# MAGI_sSensor.net
KiCad netlist of a schematic drawn in Altium Designer
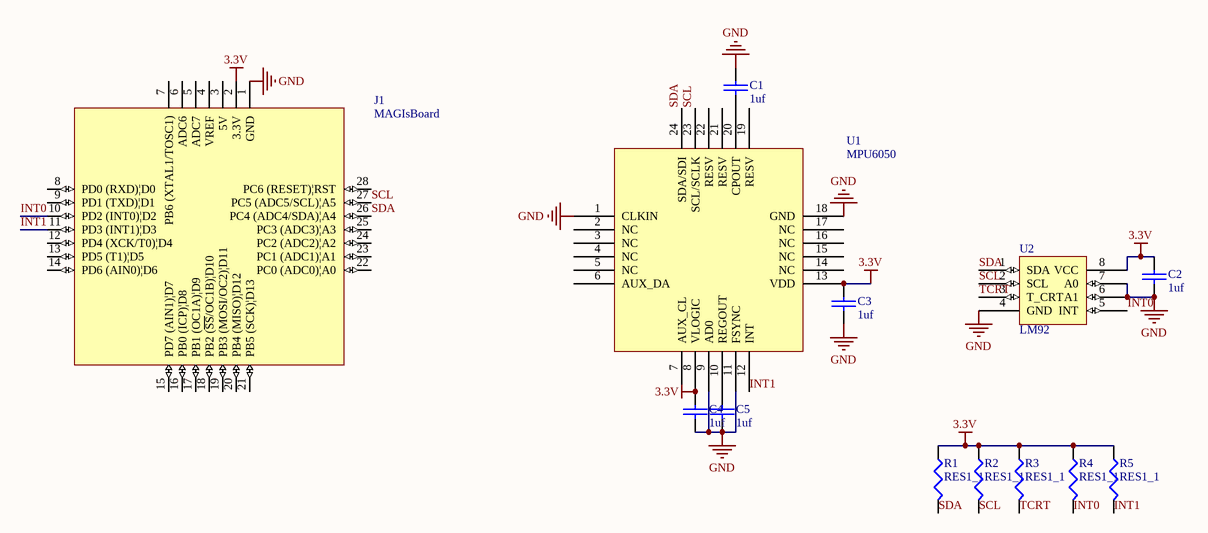
[diagram p0: MAGI'sSensor.SchDoc]

(export (version "E")
  (design (tool "Eeschema 10.0.6"))
  (components
    (comp (ref "C1")
      (value "1uf")
      (footprint "6-0805_N")
      (description "Capacitor")
      (libsource (lib "电容器") (part "CAP_1"))
    )
    (comp (ref "C2")
      (value "1uf")
      (footprint "6-0805_N")
      (description "Capacitor")
      (libsource (lib "电容器") (part "CAP_1"))
    )
    (comp (ref "C3")
      (value "1uf")
      (footprint "6-0805_N")
      (description "Capacitor")
      (libsource (lib "电容器") (part "CAP_1"))
    )
    (comp (ref "C4")
      (value "1uf")
      (footprint "6-0805_N")
      (description "Capacitor")
      (libsource (lib "电容器") (part "CAP_1"))
    )
    (comp (ref "C5")
      (value "1uf")
      (footprint "6-0805_N")
      (description "Capacitor")
      (libsource (lib "电容器") (part "CAP_1"))
    )
    (comp (ref "J1")
      (value "MAGIsBoard")
      (footprint "MAGIsBoard")
      (libsource (lib "MAGIsBoard") (part "MAGIsBoard"))
    )
    (comp (ref "R1") (value "RES1_1") (footprint "6-0805_N") (libsource (lib "电阻器") (part "RES1_1")))
    (comp (ref "R2") (value "RES1_1") (footprint "6-0805_N") (libsource (lib "电阻器") (part "RES1_1")))
    (comp (ref "R3") (value "RES1_1") (footprint "6-0805_N") (libsource (lib "电阻器") (part "RES1_1")))
    (comp (ref "R4") (value "RES1_1") (footprint "6-0805_N") (libsource (lib "电阻器") (part "RES1_1")))
    (comp (ref "R5") (value "RES1_1") (footprint "6-0805_N") (libsource (lib "电阻器") (part "RES1_1")))
    (comp (ref "U1") (value "MPU6050") (footprint "MPU6050") (libsource (lib "Sensor") (part "MPU6050")))
    (comp (ref "U2") (value "LM92") (footprint "8S1_N") (libsource (lib "ATtiny13A") (part "ATtiny13A")))
  )
  (nets
    (net (code "1") (name "/INT0") (class "Default")
      (node (ref "J1") (pin "10") (pinfunction "PD2_(INT0)¦D2_10") (pintype "bidirectional"))
      (node (ref "R4") (pin "2") (pinfunction "2_2") (pintype "passive"))
      (node (ref "U2") (pin "5") (pinfunction "INT_5") (pintype "bidirectional"))
    )
    (net (code "2") (name "/INT1") (class "Default")
      (node (ref "J1") (pin "11") (pinfunction "PD3_(INT1)¦D3_11") (pintype "bidirectional"))
      (node (ref "R5") (pin "2") (pinfunction "2_2") (pintype "passive"))
      (node (ref "U1") (pin "12") (pinfunction "INT_12") (pintype "passive"))
    )
    (net (code "3") (name "/SCL") (class "Default")
      (node (ref "J1") (pin "27") (pinfunction "PC5_(ADC5/SCL)¦A5_27") (pintype "bidirectional"))
      (node (ref "R2") (pin "2") (pinfunction "2_2") (pintype "passive"))
      (node (ref "U1") (pin "23") (pinfunction "SCL/SCLK_23") (pintype "passive"))
      (node (ref "U2") (pin "2") (pinfunction "SCL_2") (pintype "bidirectional"))
    )
    (net (code "4") (name "/SDA") (class "Default")
      (node (ref "J1") (pin "26") (pinfunction "PC4_(ADC4/SDA)¦A4_26") (pintype "bidirectional"))
      (node (ref "R1") (pin "2") (pinfunction "2_2") (pintype "passive"))
      (node (ref "U1") (pin "24") (pinfunction "SDA/SDI_24") (pintype "passive"))
      (node (ref "U2") (pin "1") (pinfunction "SDA_1") (pintype "bidirectional"))
    )
    (net (code "5") (name "/TCRT") (class "Default")
      (node (ref "R3") (pin "2") (pinfunction "2_2") (pintype "passive"))
      (node (ref "U2") (pin "3") (pinfunction "T_CRT_3") (pintype "bidirectional"))
    )
    (net (code "6") (name "3.3V") (class "Default")
      (node (ref "C2") (pin "2") (pinfunction "2_2") (pintype "passive"))
      (node (ref "C3") (pin "2") (pinfunction "2_2") (pintype "passive"))
      (node (ref "C4") (pin "2") (pinfunction "2_2") (pintype "passive"))
      (node (ref "J1") (pin "2") (pinfunction "3.3V_2") (pintype "power_in"))
      (node (ref "R1") (pin "1") (pinfunction "1_1") (pintype "passive"))
      (node (ref "R2") (pin "1") (pinfunction "1_1") (pintype "passive"))
      (node (ref "R3") (pin "1") (pinfunction "1_1") (pintype "passive"))
      (node (ref "R4") (pin "1") (pinfunction "1_1") (pintype "passive"))
      (node (ref "R5") (pin "1") (pinfunction "1_1") (pintype "passive"))
      (node (ref "U1") (pin "13") (pinfunction "VDD_13") (pintype "passive"))
      (node (ref "U1") (pin "8") (pinfunction "VLOGIC_8") (pintype "passive"))
      (node (ref "U2") (pin "8") (pinfunction "VCC_8") (pintype "power_in"))
    )
    (net (code "7") (name "GND") (class "Default")
      (node (ref "C1") (pin "1") (pinfunction "1_1") (pintype "passive"))
      (node (ref "C2") (pin "1") (pinfunction "1_1") (pintype "passive"))
      (node (ref "C3") (pin "1") (pinfunction "1_1") (pintype "passive"))
      (node (ref "C4") (pin "1") (pinfunction "1_1") (pintype "passive"))
      (node (ref "C5") (pin "1") (pinfunction "1_1") (pintype "passive"))
      (node (ref "J1") (pin "1") (pinfunction "GND_1") (pintype "power_in"))
      (node (ref "U1") (pin "1") (pinfunction "CLKIN_1") (pintype "passive"))
      (node (ref "U1") (pin "11") (pinfunction "FSYNC_11") (pintype "passive"))
      (node (ref "U1") (pin "18") (pinfunction "GND_18") (pintype "passive"))
      (node (ref "U1") (pin "9") (pinfunction "AD0_9") (pintype "passive"))
      (node (ref "U2") (pin "4") (pinfunction "GND_4") (pintype "power_in"))
      (node (ref "U2") (pin "6") (pinfunction "A1_6") (pintype "bidirectional"))
      (node (ref "U2") (pin "7") (pinfunction "A0_7") (pintype "bidirectional"))
    )
    (net (code "8") (name "Net-(U1-CPOUT)") (class "Default")
      (node (ref "C1") (pin "2") (pinfunction "2_2") (pintype "passive"))
      (node (ref "U1") (pin "20") (pinfunction "CPOUT_20") (pintype "passive"))
    )
    (net (code "9") (name "Net-(U1-REGOUT)") (class "Default")
      (node (ref "C5") (pin "2") (pinfunction "2_2") (pintype "passive"))
      (node (ref "U1") (pin "10") (pinfunction "REGOUT_10") (pintype "passive"))
    )
    (net (code "10") (name "unconnected-(J1-5V-Pad3)") (class "Default")
      (node (ref "J1") (pin "3") (pinfunction "5V_3") (pintype "power_in"))
    )
    (net (code "11") (name "unconnected-(J1-ADC6-Pad6)") (class "Default")
      (node (ref "J1") (pin "6") (pinfunction "ADC6_6") (pintype "passive"))
    )
    (net (code "12") (name "unconnected-(J1-ADC7-Pad5)") (class "Default")
      (node (ref "J1") (pin "5") (pinfunction "ADC7_5") (pintype "passive"))
    )
    (net (code "13") (name "unconnected-(J1-PB0_(ICP)¦D8-Pad16)") (class "Default")
      (node (ref "J1") (pin "16") (pinfunction "PB0_(ICP)¦D8_16") (pintype "bidirectional"))
    )
    (net (code "14") (name "unconnected-(J1-PB1_(OC1A)¦D9-Pad17)") (class "Default")
      (node (ref "J1") (pin "17") (pinfunction "PB1_(OC1A)¦D9_17") (pintype "bidirectional"))
    )
    (net (code "15") (name "unconnected-(J1-PB2_(~{SS}{slash}OC1B)¦D10-Pad18)") (class "Default")
      (node (ref "J1") (pin "18") (pinfunction "PB2_(~{SS}/OC1B)¦D10_18") (pintype "bidirectional"))
    )
    (net (code "16") (name "unconnected-(J1-PB3_(MOSI{slash}OC2)¦D11-Pad19)") (class "Default")
      (node (ref "J1") (pin "19") (pinfunction "PB3_(MOSI/OC2)¦D11_19") (pintype "bidirectional"))
    )
    (net (code "17") (name "unconnected-(J1-PB4_(MISO)¦D12-Pad20)") (class "Default")
      (node (ref "J1") (pin "20") (pinfunction "PB4_(MISO)¦D12_20") (pintype "bidirectional"))
    )
    (net (code "18") (name "unconnected-(J1-PB5_(SCK)¦D13-Pad21)") (class "Default")
      (node (ref "J1") (pin "21") (pinfunction "PB5_(SCK)¦D13_21") (pintype "bidirectional"))
    )
    (net (code "19") (name "unconnected-(J1-PB6_(XTAL1{slash}TOSC1)-Pad7)") (class "Default")
      (node (ref "J1") (pin "7") (pinfunction "PB6_(XTAL1/TOSC1)_7") (pintype "passive"))
    )
    (net (code "20") (name "unconnected-(J1-PC0_(ADC0)¦A0-Pad22)") (class "Default")
      (node (ref "J1") (pin "22") (pinfunction "PC0_(ADC0)¦A0_22") (pintype "bidirectional"))
    )
    (net (code "21") (name "unconnected-(J1-PC1_(ADC1)¦A1-Pad23)") (class "Default")
      (node (ref "J1") (pin "23") (pinfunction "PC1_(ADC1)¦A1_23") (pintype "bidirectional"))
    )
    (net (code "22") (name "unconnected-(J1-PC2_(ADC2)¦A2-Pad24)") (class "Default")
      (node (ref "J1") (pin "24") (pinfunction "PC2_(ADC2)¦A2_24") (pintype "bidirectional"))
    )
    (net (code "23") (name "unconnected-(J1-PC3_(ADC3)¦A3-Pad25)") (class "Default")
      (node (ref "J1") (pin "25") (pinfunction "PC3_(ADC3)¦A3_25") (pintype "bidirectional"))
    )
    (net (code "24") (name "unconnected-(J1-PC6_(RESET)¦RST-Pad28)") (class "Default")
      (node (ref "J1") (pin "28") (pinfunction "PC6_(RESET)¦RST_28") (pintype "bidirectional"))
    )
    (net (code "25") (name "unconnected-(J1-PD0_(RXD)¦D0-Pad8)") (class "Default")
      (node (ref "J1") (pin "8") (pinfunction "PD0_(RXD)¦D0_8") (pintype "bidirectional"))
    )
    (net (code "26") (name "unconnected-(J1-PD1_(TXD)¦D1-Pad9)") (class "Default")
      (node (ref "J1") (pin "9") (pinfunction "PD1_(TXD)¦D1_9") (pintype "bidirectional"))
    )
    (net (code "27") (name "unconnected-(J1-PD4_(XCK{slash}T0)¦D4-Pad12)") (class "Default")
      (node (ref "J1") (pin "12") (pinfunction "PD4_(XCK/T0)¦D4_12") (pintype "bidirectional"))
    )
    (net (code "28") (name "unconnected-(J1-PD5_(T1)¦D5-Pad13)") (class "Default")
      (node (ref "J1") (pin "13") (pinfunction "PD5_(T1)¦D5_13") (pintype "bidirectional"))
    )
    (net (code "29") (name "unconnected-(J1-PD6_(AIN0)¦D6-Pad14)") (class "Default")
      (node (ref "J1") (pin "14") (pinfunction "PD6_(AIN0)¦D6_14") (pintype "bidirectional"))
    )
    (net (code "30") (name "unconnected-(J1-PD7_(AIN1)¦D7-Pad15)") (class "Default")
      (node (ref "J1") (pin "15") (pinfunction "PD7_(AIN1)¦D7_15") (pintype "bidirectional"))
    )
    (net (code "31") (name "unconnected-(J1-VREF-Pad4)") (class "Default")
      (node (ref "J1") (pin "4") (pinfunction "VREF_4") (pintype "passive"))
    )
    (net (code "32") (name "unconnected-(U1-AUX_CL-Pad7)") (class "Default")
      (node (ref "U1") (pin "7") (pinfunction "AUX_CL_7") (pintype "passive"))
    )
    (net (code "33") (name "unconnected-(U1-AUX_DA-Pad6)") (class "Default")
      (node (ref "U1") (pin "6") (pinfunction "AUX_DA_6") (pintype "passive"))
    )
    (net (code "34") (name "unconnected-(U1-NC-Pad2)") (class "Default")
      (node (ref "U1") (pin "2") (pinfunction "NC_2") (pintype "passive"))
    )
    (net (code "35") (name "unconnected-(U1-NC-Pad3)") (class "Default")
      (node (ref "U1") (pin "3") (pinfunction "NC_3") (pintype "passive"))
    )
    (net (code "36") (name "unconnected-(U1-NC-Pad4)") (class "Default")
      (node (ref "U1") (pin "4") (pinfunction "NC_4") (pintype "passive"))
    )
    (net (code "37") (name "unconnected-(U1-NC-Pad5)") (class "Default")
      (node (ref "U1") (pin "5") (pinfunction "NC_5") (pintype "passive"))
    )
    (net (code "38") (name "unconnected-(U1-NC-Pad14)") (class "Default")
      (node (ref "U1") (pin "14") (pinfunction "NC_14") (pintype "passive"))
    )
    (net (code "39") (name "unconnected-(U1-NC-Pad15)") (class "Default")
      (node (ref "U1") (pin "15") (pinfunction "NC_15") (pintype "passive"))
    )
    (net (code "40") (name "unconnected-(U1-NC-Pad16)") (class "Default")
      (node (ref "U1") (pin "16") (pinfunction "NC_16") (pintype "passive"))
    )
    (net (code "41") (name "unconnected-(U1-NC-Pad17)") (class "Default")
      (node (ref "U1") (pin "17") (pinfunction "NC_17") (pintype "passive"))
    )
    (net (code "42") (name "unconnected-(U1-RESV-Pad19)") (class "Default")
      (node (ref "U1") (pin "19") (pinfunction "RESV_19") (pintype "passive"))
    )
    (net (code "43") (name "unconnected-(U1-RESV-Pad21)") (class "Default")
      (node (ref "U1") (pin "21") (pinfunction "RESV_21") (pintype "passive"))
    )
    (net (code "44") (name "unconnected-(U1-RESV-Pad22)") (class "Default")
      (node (ref "U1") (pin "22") (pinfunction "RESV_22") (pintype "passive"))
    )
  )
)
